# evpr_mainboard.net
KiCad netlist of a schematic drawn in EAGLE
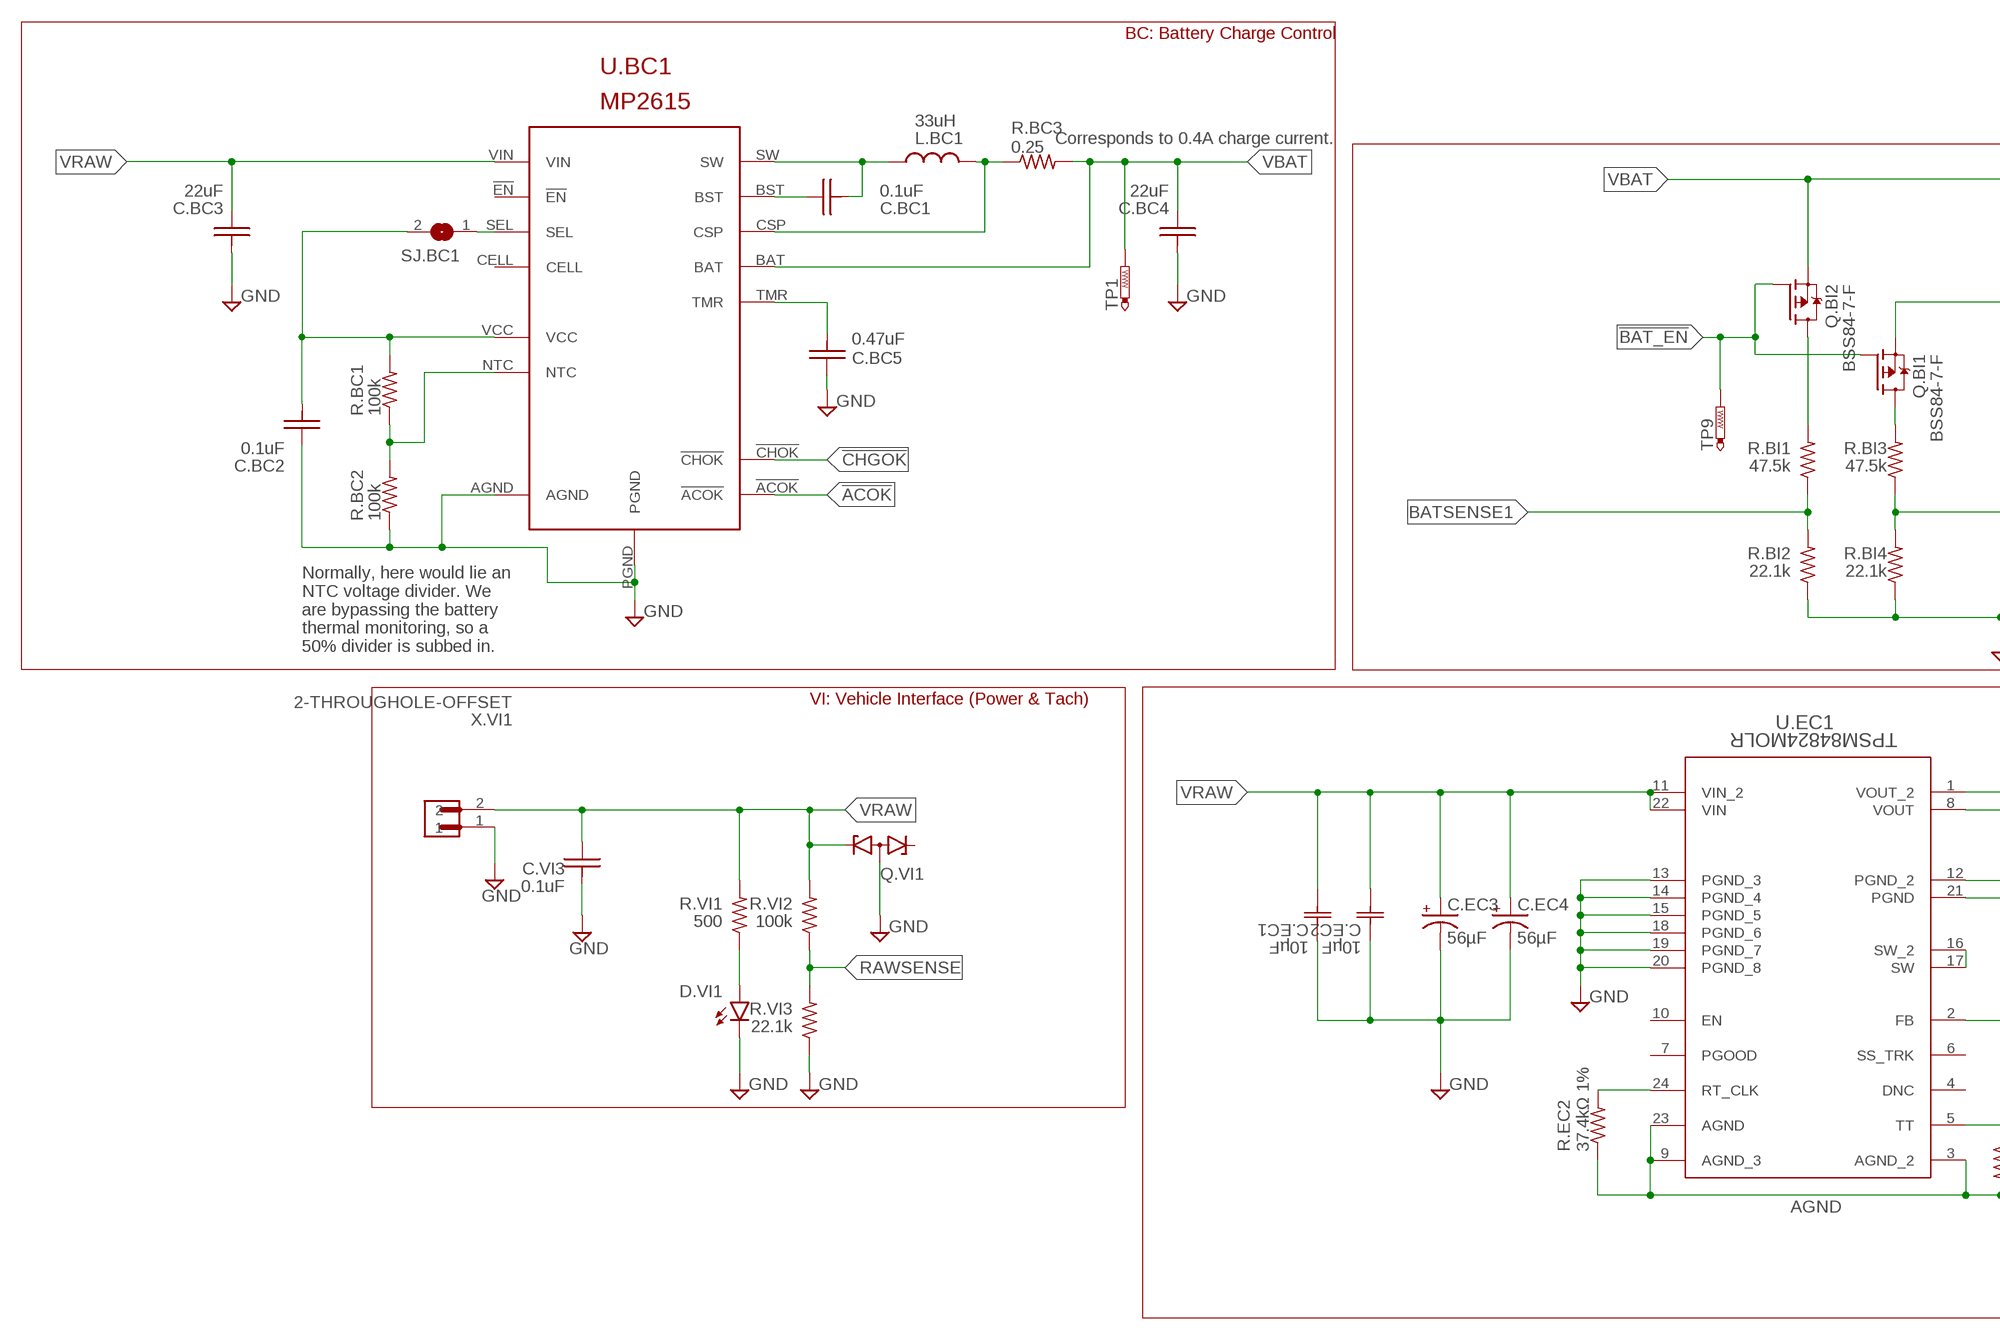
[diagram p0: schematic, sheet 1, part 1 of 2]
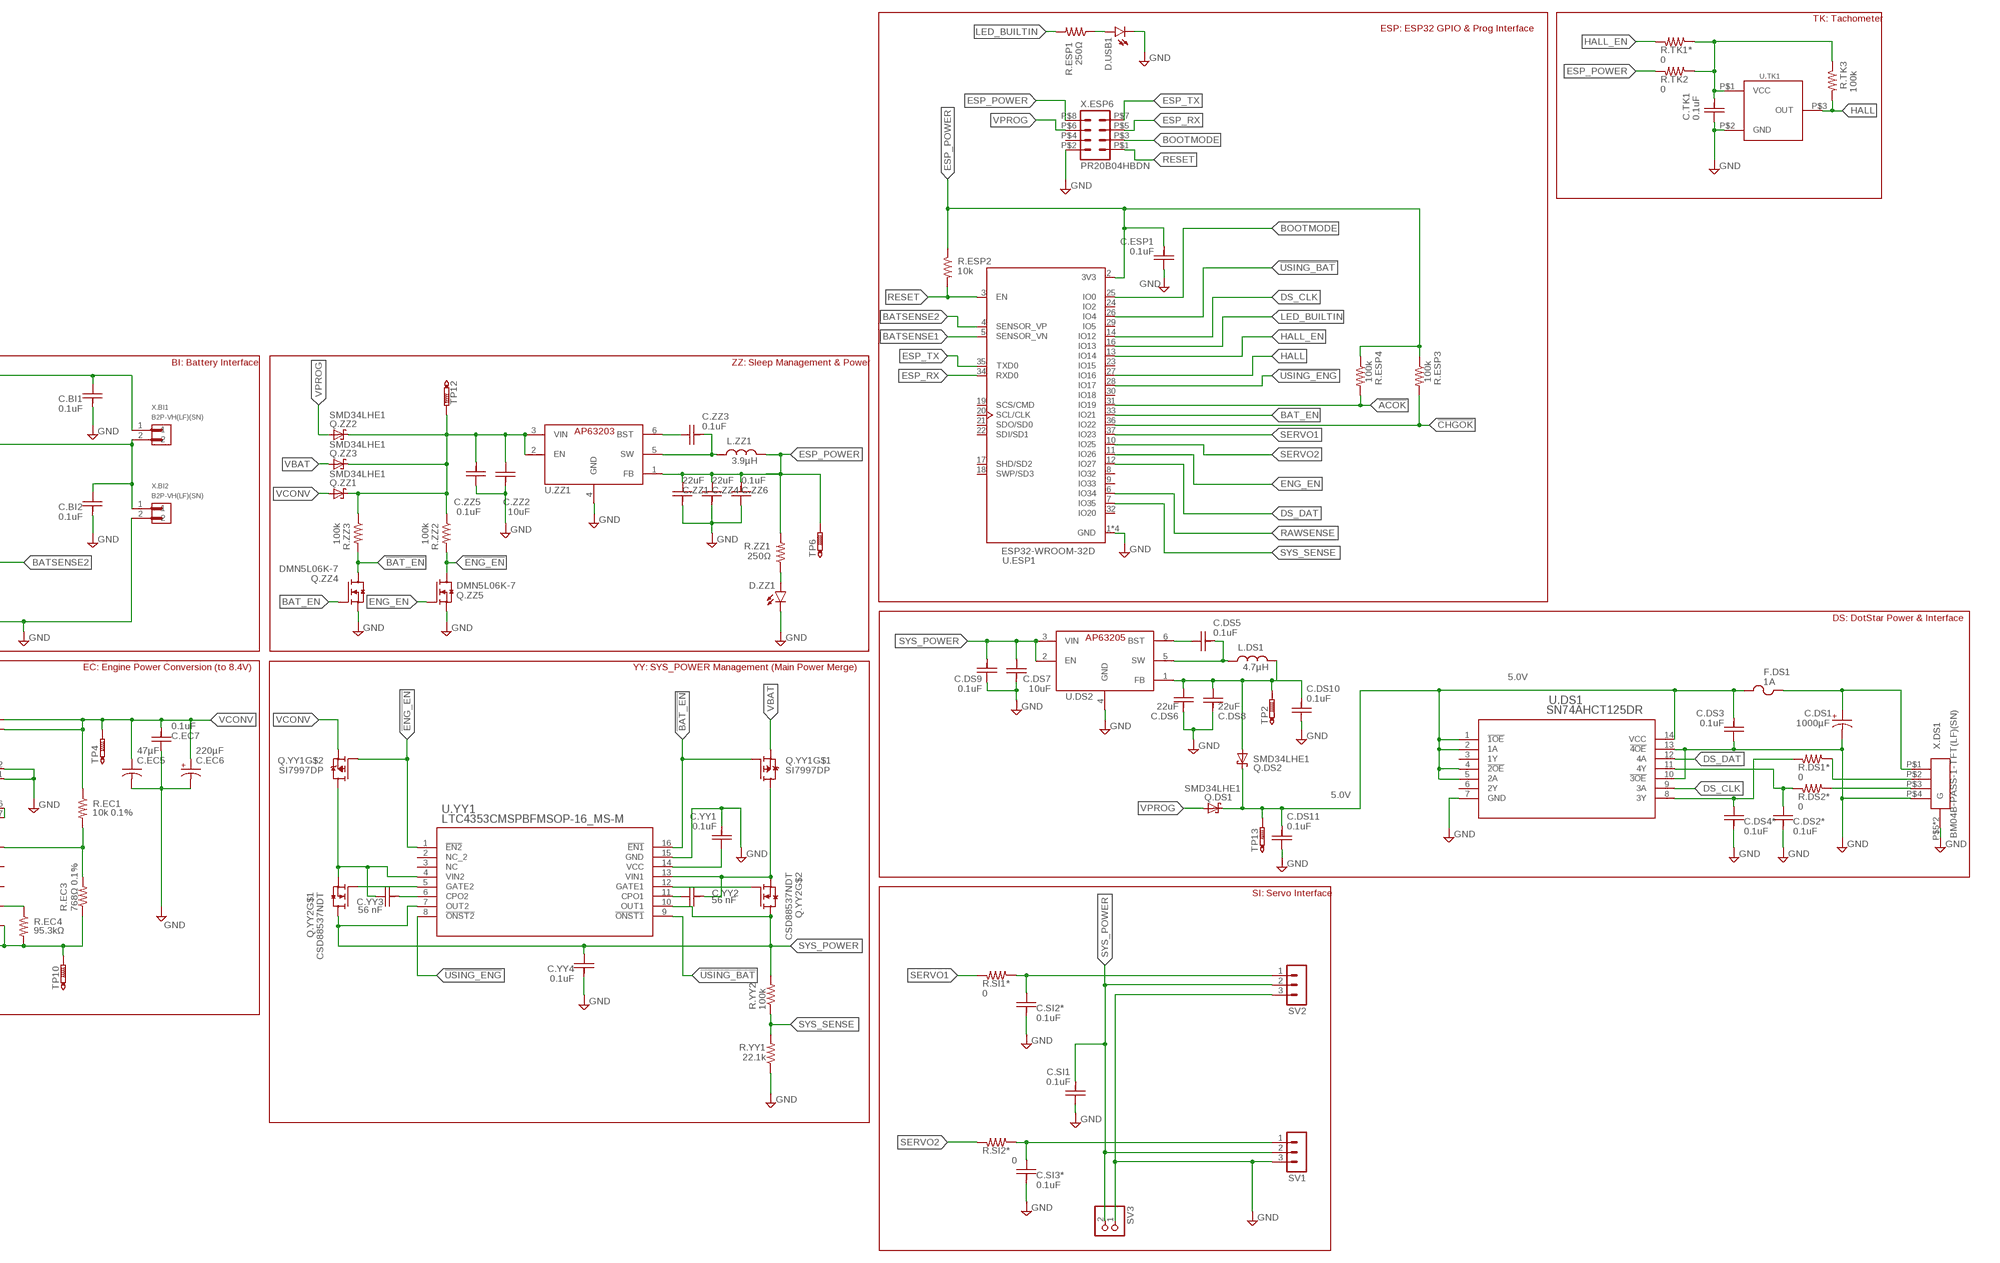
[diagram p1: schematic, sheet 1, part 2 of 2]

(export (version "E")
  (design (tool "Eeschema 10.0.6"))
  (components
    (comp (ref "C.BC1")
      (value "0.1uF")
      (footprint "eagle-import:C0603")
      (libsource (lib "eagle-import") (part "C0603"))
    )
    (comp (ref "C.BC2")
      (value "0.1uF")
      (footprint "eagle-import:C0603")
      (libsource (lib "eagle-import") (part "C0603"))
    )
    (comp (ref "C.BC3")
      (value "22uF")
      (footprint "eagle-import:C0603")
      (libsource (lib "eagle-import") (part "C0603"))
    )
    (comp (ref "C.BC4")
      (value "22uF")
      (footprint "eagle-import:C0603")
      (libsource (lib "eagle-import") (part "C0603"))
    )
    (comp (ref "C.BC5")
      (value "0.47uF")
      (footprint "eagle-import:C0603")
      (libsource (lib "eagle-import") (part "C0603"))
    )
    (comp (ref "C.BI1")
      (value "0.1uF")
      (footprint "eagle-import:C0603")
      (libsource (lib "eagle-import") (part "C0603"))
    )
    (comp (ref "C.BI2")
      (value "0.1uF")
      (footprint "eagle-import:C0603")
      (libsource (lib "eagle-import") (part "C0603"))
    )
    (comp (ref "C.DS1")
      (value "1000µF")
      (footprint "eagle-import:810RADCAN")
      (libsource (lib "eagle-import") (part "810RADCAP"))
    )
    (comp (ref "C.DS2*")
      (value "0.1uF")
      (footprint "eagle-import:C0603")
      (libsource (lib "eagle-import") (part "C0603"))
    )
    (comp (ref "C.DS3")
      (value "0.1uF")
      (footprint "eagle-import:C0603")
      (libsource (lib "eagle-import") (part "C0603"))
    )
    (comp (ref "C.DS4*")
      (value "0.1uF")
      (footprint "eagle-import:C0603")
      (libsource (lib "eagle-import") (part "C0603"))
    )
    (comp (ref "C.DS5")
      (value "0.1uF")
      (footprint "eagle-import:C0603")
      (libsource (lib "eagle-import") (part "C0603"))
    )
    (comp (ref "C.DS6")
      (value "22uF")
      (footprint "eagle-import:C0603")
      (libsource (lib "eagle-import") (part "C0603"))
    )
    (comp (ref "C.DS7")
      (value "10uF")
      (footprint "eagle-import:C0603")
      (libsource (lib "eagle-import") (part "C0603"))
    )
    (comp (ref "C.DS8")
      (value "22uF")
      (footprint "eagle-import:C0603")
      (libsource (lib "eagle-import") (part "C0603"))
    )
    (comp (ref "C.DS9")
      (value "0.1uF")
      (footprint "eagle-import:C0603")
      (libsource (lib "eagle-import") (part "C0603"))
    )
    (comp (ref "C.DS10")
      (value "0.1uF")
      (footprint "eagle-import:C0603")
      (libsource (lib "eagle-import") (part "C0603"))
    )
    (comp (ref "C.DS11")
      (value "0.1uF")
      (footprint "eagle-import:C0603")
      (libsource (lib "eagle-import") (part "C0603"))
    )
    (comp (ref "C.EC1")
      (value "10µF")
      (footprint "eagle-import:CAP_3225")
      (libsource (lib "eagle-import") (part "C3225X7R1E106K250AC"))
    )
    (comp (ref "C.EC2")
      (value "10µF")
      (footprint "eagle-import:CAP_3225")
      (libsource (lib "eagle-import") (part "C3225X7R1E106K250AC"))
    )
    (comp (ref "C.EC3")
      (value "56µF")
      (footprint "eagle-import:OSCON_SVPF_6.3MM")
      (libsource (lib "eagle-import") (part "6.3MMCAP"))
    )
    (comp (ref "C.EC4")
      (value "56µF")
      (footprint "eagle-import:OSCON_SVPF_6.3MM")
      (libsource (lib "eagle-import") (part "6.3MMCAP"))
    )
    (comp (ref "C.EC5")
      (value "47µF")
      (footprint "eagle-import:C1210")
      (libsource (lib "eagle-import") (part "C-USC1210"))
    )
    (comp (ref "C.EC6")
      (value "220µF")
      (footprint "eagle-import:C6CYLCAP")
      (libsource (lib "eagle-import") (part "WURTH875115352003"))
    )
    (comp (ref "C.EC7")
      (value "0.1uF")
      (footprint "eagle-import:C0603")
      (libsource (lib "eagle-import") (part "C0603"))
    )
    (comp (ref "C.ESP1")
      (value "0.1uF")
      (footprint "eagle-import:C0603")
      (libsource (lib "eagle-import") (part "C0603"))
    )
    (comp (ref "C.SI1")
      (value "0.1uF")
      (footprint "eagle-import:C0603")
      (libsource (lib "eagle-import") (part "C0603"))
    )
    (comp (ref "C.SI2*")
      (value "0.1uF")
      (footprint "eagle-import:C0603")
      (libsource (lib "eagle-import") (part "C0603"))
    )
    (comp (ref "C.SI3*")
      (value "0.1uF")
      (footprint "eagle-import:C0603")
      (libsource (lib "eagle-import") (part "C0603"))
    )
    (comp (ref "C.TK1")
      (value "0.1uF")
      (footprint "eagle-import:C0603")
      (libsource (lib "eagle-import") (part "C0603"))
    )
    (comp (ref "C.VI3")
      (value "0.1uF")
      (footprint "eagle-import:C0603")
      (libsource (lib "eagle-import") (part "C0603"))
    )
    (comp (ref "C.YY1")
      (value "0.1uF")
      (footprint "eagle-import:C0603")
      (libsource (lib "eagle-import") (part "C0603"))
    )
    (comp (ref "C.YY2")
      (value "56 nF")
      (footprint "eagle-import:C0603")
      (libsource (lib "eagle-import") (part "C0603"))
    )
    (comp (ref "C.YY3")
      (value "56 nF")
      (footprint "eagle-import:C0603")
      (libsource (lib "eagle-import") (part "C0603"))
    )
    (comp (ref "C.YY4")
      (value "0.1uF")
      (footprint "eagle-import:C0603")
      (libsource (lib "eagle-import") (part "C0603"))
    )
    (comp (ref "C.ZZ1")
      (value "22uF")
      (footprint "eagle-import:C0603")
      (libsource (lib "eagle-import") (part "C0603"))
    )
    (comp (ref "C.ZZ2")
      (value "10uF")
      (footprint "eagle-import:C0603")
      (libsource (lib "eagle-import") (part "C0603"))
    )
    (comp (ref "C.ZZ3")
      (value "0.1uF")
      (footprint "eagle-import:C0603")
      (libsource (lib "eagle-import") (part "C0603"))
    )
    (comp (ref "C.ZZ4")
      (value "22uF")
      (footprint "eagle-import:C0603")
      (libsource (lib "eagle-import") (part "C0603"))
    )
    (comp (ref "C.ZZ5")
      (value "0.1uF")
      (footprint "eagle-import:C0603")
      (libsource (lib "eagle-import") (part "C0603"))
    )
    (comp (ref "C.ZZ6")
      (value "0.1uF")
      (footprint "eagle-import:C0603")
      (libsource (lib "eagle-import") (part "C0603"))
    )
    (comp (ref "D.USB1")
      (value "LEDCHIP-LED0805")
      (footprint "eagle-import:CHIP-LED0805")
      (libsource (lib "eagle-import") (part "LEDCHIP-LED0805"))
    )
    (comp (ref "D.VI1")
      (value "LEDCHIP-LED0805")
      (footprint "eagle-import:CHIP-LED0805")
      (libsource (lib "eagle-import") (part "LEDCHIP-LED0805"))
    )
    (comp (ref "D.ZZ1")
      (value "LEDCHIP-LED0805")
      (footprint "eagle-import:CHIP-LED0805")
      (libsource (lib "eagle-import") (part "LEDCHIP-LED0805"))
    )
    (comp (ref "F.DS1")
      (value "1A")
      (footprint "eagle-import:C1-M")
      (fields (field (name "MANUFACTURER_PART_NUMBER") "C1Q 1"))
      (libsource (lib "eagle-import") (part "C1Q_1C1-M"))
    )
    (comp (ref "L.BC1")
      (value "33uH")
      (footprint "eagle-import:SRN5040TA")
      (libsource (lib "eagle-import") (part "SRN5040TA-330M"))
    )
    (comp (ref "L.DS1")
      (value "4.7µH")
      (footprint "eagle-import:SRR4818A-XXXX")
      (libsource (lib "eagle-import") (part "SRR4818A-XXXX"))
    )
    (comp (ref "L.ZZ1")
      (value "3.9µH")
      (footprint "eagle-import:SRR4818A-XXXX")
      (libsource (lib "eagle-import") (part "SRR4818A-XXXX"))
    )
    (comp (ref "Q.BI1")
      (value "BSS84-7-F")
      (footprint "eagle-import:SOT23")
      (libsource (lib "eagle-import") (part "BSS84-7-F"))
    )
    (comp (ref "Q.BI2")
      (value "BSS84-7-F")
      (footprint "eagle-import:SOT23")
      (libsource (lib "eagle-import") (part "BSS84-7-F"))
    )
    (comp (ref "Q.DS1")
      (value "SMD34LHE1")
      (footprint "eagle-import:SOD-123HE1")
      (libsource (lib "eagle-import") (part "SMD34LHE1"))
    )
    (comp (ref "Q.DS2")
      (value "SMD34LHE1")
      (footprint "eagle-import:SOD-123HE1")
      (libsource (lib "eagle-import") (part "SMD34LHE1"))
    )
    (comp (ref "Q.VI1")
      (value "VESD16A2-03G-G3-08")
      (footprint "eagle-import:SOT23")
      (libsource (lib "eagle-import") (part "VESD16A2-03G-G3-08"))
    )
    (comp (ref "Q.YY1")
      (value "SI7997DP")
      (footprint "eagle-import:POWERPAK_SO8DUAL")
      (libsource (lib "eagle-import") (part "SI7997DP"))
    )
    (comp (ref "Q.YY2")
      (value "CSD88537NDT")
      (footprint "eagle-import:SOIC8")
      (fields (field (name "COMPONENT") "CSD88537NDT"))
      (libsource (lib "eagle-import") (part "CSD88537NDT"))
    )
    (comp (ref "Q.ZZ1")
      (value "SMD34LHE1")
      (footprint "eagle-import:SOD-123HE1")
      (libsource (lib "eagle-import") (part "SMD34LHE1"))
    )
    (comp (ref "Q.ZZ2")
      (value "SMD34LHE1")
      (footprint "eagle-import:SOD-123HE1")
      (libsource (lib "eagle-import") (part "SMD34LHE1"))
    )
    (comp (ref "Q.ZZ3")
      (value "SMD34LHE1")
      (footprint "eagle-import:SOD-123HE1")
      (libsource (lib "eagle-import") (part "SMD34LHE1"))
    )
    (comp (ref "Q.ZZ4")
      (value "DMN5L06K-7")
      (footprint "eagle-import:SOT23")
      (libsource (lib "eagle-import") (part "DMN5L06K-7"))
    )
    (comp (ref "Q.ZZ5")
      (value "DMN5L06K-7")
      (footprint "eagle-import:SOT23")
      (libsource (lib "eagle-import") (part "DMN5L06K-7"))
    )
    (comp (ref "R.BC1")
      (value "100k")
      (footprint "eagle-import:R0603")
      (libsource (lib "eagle-import") (part "R0603"))
    )
    (comp (ref "R.BC2")
      (value "100k")
      (footprint "eagle-import:R0603")
      (libsource (lib "eagle-import") (part "R0603"))
    )
    (comp (ref "R.BC3")
      (value "0.25")
      (footprint "eagle-import:R0603")
      (libsource (lib "eagle-import") (part "R0603"))
    )
    (comp (ref "R.BI1")
      (value "47.5k")
      (footprint "eagle-import:R0603")
      (libsource (lib "eagle-import") (part "R0603"))
    )
    (comp (ref "R.BI2")
      (value "22.1k")
      (footprint "eagle-import:R0603")
      (libsource (lib "eagle-import") (part "R0603"))
    )
    (comp (ref "R.BI3")
      (value "47.5k")
      (footprint "eagle-import:R0603")
      (libsource (lib "eagle-import") (part "R0603"))
    )
    (comp (ref "R.BI4")
      (value "22.1k")
      (footprint "eagle-import:R0603")
      (libsource (lib "eagle-import") (part "R0603"))
    )
    (comp (ref "R.DS1*")
      (value "0")
      (footprint "eagle-import:R0603")
      (libsource (lib "eagle-import") (part "R0603"))
    )
    (comp (ref "R.DS2*")
      (value "0")
      (footprint "eagle-import:R0603")
      (libsource (lib "eagle-import") (part "R0603"))
    )
    (comp (ref "R.EC1")
      (value "10k 0.1%")
      (footprint "eagle-import:R0603")
      (libsource (lib "eagle-import") (part "R0603"))
    )
    (comp (ref "R.EC2")
      (value "37.4kΩ 1%")
      (footprint "eagle-import:R0603")
      (libsource (lib "eagle-import") (part "R0603"))
    )
    (comp (ref "R.EC3")
      (value "768Ω 0.1%")
      (footprint "eagle-import:R0603")
      (libsource (lib "eagle-import") (part "R0603"))
    )
    (comp (ref "R.EC4")
      (value "95.3kΩ")
      (footprint "eagle-import:R0603")
      (libsource (lib "eagle-import") (part "R0603"))
    )
    (comp (ref "R.ESP1")
      (value "250Ω")
      (footprint "eagle-import:R0603")
      (libsource (lib "eagle-import") (part "R0603"))
    )
    (comp (ref "R.ESP2")
      (value "10k")
      (footprint "eagle-import:R0603")
      (libsource (lib "eagle-import") (part "R0603"))
    )
    (comp (ref "R.ESP3")
      (value "100k")
      (footprint "eagle-import:R0603")
      (libsource (lib "eagle-import") (part "R0603"))
    )
    (comp (ref "R.ESP4")
      (value "100k")
      (footprint "eagle-import:R0603")
      (libsource (lib "eagle-import") (part "R0603"))
    )
    (comp (ref "R.SI1*")
      (value "0")
      (footprint "eagle-import:R0603")
      (libsource (lib "eagle-import") (part "R0603"))
    )
    (comp (ref "R.SI2*")
      (value "0")
      (footprint "eagle-import:R0603")
      (libsource (lib "eagle-import") (part "R0603"))
    )
    (comp (ref "R.TK1*")
      (value "0")
      (footprint "eagle-import:R0603")
      (libsource (lib "eagle-import") (part "R0603"))
    )
    (comp (ref "R.TK2")
      (value "0")
      (footprint "eagle-import:R0603")
      (libsource (lib "eagle-import") (part "R0603"))
    )
    (comp (ref "R.TK3")
      (value "100k")
      (footprint "eagle-import:R0603")
      (libsource (lib "eagle-import") (part "R0603"))
    )
    (comp (ref "R.VI1")
      (value "500")
      (footprint "eagle-import:R0603")
      (libsource (lib "eagle-import") (part "R0603"))
    )
    (comp (ref "R.VI2")
      (value "100k")
      (footprint "eagle-import:R0603")
      (libsource (lib "eagle-import") (part "R0603"))
    )
    (comp (ref "R.VI3")
      (value "22.1k")
      (footprint "eagle-import:R0603")
      (libsource (lib "eagle-import") (part "R0603"))
    )
    (comp (ref "R.YY1")
      (value "22.1k")
      (footprint "eagle-import:R0603")
      (libsource (lib "eagle-import") (part "R0603"))
    )
    (comp (ref "R.YY2")
      (value "100k")
      (footprint "eagle-import:R0603")
      (libsource (lib "eagle-import") (part "R0603"))
    )
    (comp (ref "R.ZZ1")
      (value "250Ω")
      (footprint "eagle-import:R0603")
      (libsource (lib "eagle-import") (part "R0603"))
    )
    (comp (ref "R.ZZ2")
      (value "100k")
      (footprint "eagle-import:R0603")
      (libsource (lib "eagle-import") (part "R0603"))
    )
    (comp (ref "R.ZZ3")
      (value "100k")
      (footprint "eagle-import:R0603")
      (libsource (lib "eagle-import") (part "R0603"))
    )
    (comp (ref "SJ.BC1")
      (value "SJ")
      (footprint "eagle-import:SJ")
      (libsource (lib "eagle-import") (part "SJ"))
    )
    (comp (ref "SV1")
      (value "MA03-1")
      (footprint "eagle-import:MA03-1")
      (libsource (lib "eagle-import") (part "MA03-1"))
    )
    (comp (ref "SV2")
      (value "MA03-1")
      (footprint "eagle-import:MA03-1")
      (libsource (lib "eagle-import") (part "MA03-1"))
    )
    (comp (ref "SV3")
      (value "PINHD-1X2")
      (footprint "eagle-import:1X02")
      (libsource (lib "eagle-import") (part "PINHD-1X2"))
    )
    (comp (ref "TP1")
      (value "PTR1TP10R")
      (footprint "eagle-import:TP10R")
      (libsource (lib "eagle-import") (part "PTR1TP10R"))
    )
    (comp (ref "TP2")
      (value "PTR1TP10R")
      (footprint "eagle-import:TP10R")
      (libsource (lib "eagle-import") (part "PTR1TP10R"))
    )
    (comp (ref "TP4")
      (value "PTR1TP10R")
      (footprint "eagle-import:TP10R")
      (libsource (lib "eagle-import") (part "PTR1TP10R"))
    )
    (comp (ref "TP6")
      (value "PTR1TP10R")
      (footprint "eagle-import:TP10R")
      (libsource (lib "eagle-import") (part "PTR1TP10R"))
    )
    (comp (ref "TP9")
      (value "PTR1TP10R")
      (footprint "eagle-import:TP10R")
      (libsource (lib "eagle-import") (part "PTR1TP10R"))
    )
    (comp (ref "TP10")
      (value "PTR1TP10R")
      (footprint "eagle-import:TP10R")
      (libsource (lib "eagle-import") (part "PTR1TP10R"))
    )
    (comp (ref "TP12")
      (value "PTR1TP10R")
      (footprint "eagle-import:TP10R")
      (libsource (lib "eagle-import") (part "PTR1TP10R"))
    )
    (comp (ref "TP13")
      (value "PTR1TP10R")
      (footprint "eagle-import:TP10R")
      (libsource (lib "eagle-import") (part "PTR1TP10R"))
    )
    (comp (ref "U.BC1")
      (value "MP2615")
      (footprint "eagle-import:QFN16")
      (libsource (lib "eagle-import") (part "MP2615"))
    )
    (comp (ref "U.DS1")
      (value "SN74AHCT125DR")
      (footprint "eagle-import:D14")
      (libsource (lib "eagle-import") (part "SN74AHCT125DR"))
    )
    (comp (ref "U.DS2")
      (value "AP63205")
      (footprint "eagle-import:TSOT23-6")
      (libsource (lib "eagle-import") (part "AP63205"))
    )
    (comp (ref "U.EC1")
      (value "TPSM84824MOLR")
      (footprint "eagle-import:MOL0024A")
      (libsource (lib "eagle-import") (part "TPSM84824MOLR"))
    )
    (comp (ref "U.ESP1")
      (value "ESP32-WROOM-32D")
      (footprint "eagle-import:MODULE_ESP32-WROOM-32D")
      (fields (field (name "MF") "Espressif Systems"))
      (libsource (lib "eagle-import") (part "ESP32-WROOM-32D"))
    )
    (comp (ref "U.TK1")
      (value "HALLEFFECT")
      (footprint "eagle-import:1.27MMHALLEFECT")
      (libsource (lib "eagle-import") (part "HALLEFFECT"))
    )
    (comp (ref "U.YY1")
      (value "LTC4353CMSPBFMSOP-16_MS-M")
      (footprint "eagle-import:MSOP-16_MS-M")
      (fields (field (name "MANUFACTURER_PART_NUMBER") "LTC4353CMS#PBF"))
      (libsource (lib "eagle-import") (part "LTC4353CMSPBFMSOP-16_MS-M"))
    )
    (comp (ref "U.ZZ1")
      (value "AP63203")
      (footprint "eagle-import:TSOT23-6")
      (libsource (lib "eagle-import") (part "AP63203"))
    )
    (comp (ref "X.BI1")
      (value "B2P-VH(LF)(SN)")
      (footprint "eagle-import:B2P-VH(LF)(SN)")
      (fields (field (name "MF") "JST Sales") (field (name "MP") "B2P-VH_LF__SN_"))
      (libsource (lib "eagle-import") (part "B2P-VH(LF)(SN)"))
    )
    (comp (ref "X.BI2")
      (value "B2P-VH(LF)(SN)")
      (footprint "eagle-import:B2P-VH(LF)(SN)")
      (fields (field (name "MF") "JST Sales") (field (name "MP") "B2P-VH_LF__SN_"))
      (libsource (lib "eagle-import") (part "B2P-VH(LF)(SN)"))
    )
    (comp (ref "X.DS1")
      (value "BM04B-PASS-1-TFT(LF)(SN)")
      (footprint "eagle-import:BM04B-PASS-1-TFT(LF)(SN)")
      (libsource (lib "eagle-import") (part "BM04B-PASS-1-TFT(LF)(SN)"))
    )
    (comp (ref "X.ESP6")
      (value "PR20B04HBDN")
      (footprint "eagle-import:PR20B04HBDN")
      (libsource (lib "eagle-import") (part "PR20B04HBDN"))
    )
    (comp (ref "X.VI1")
      (value "2-THROUGHOLE-OFFSET")
      (footprint "eagle-import:2-THROUGH-HOLE-LARGE-OFFSET")
      (libsource (lib "eagle-import") (part "2-THROUGHOLE-OFFSET"))
    )
  )
  (nets
    (net (code "1") (name "/5.0V") (class "Default")
      (node (ref "C.DS11") (pin "2") (pinfunction "2_2") (pintype "passive"))
      (node (ref "C.DS3") (pin "2") (pinfunction "2_2") (pintype "passive"))
      (node (ref "F.DS1") (pin "1") (pinfunction "1_1") (pintype "passive"))
      (node (ref "Q.DS1") (pin "C") (pinfunction "C_C") (pintype "passive"))
      (node (ref "Q.DS2") (pin "C") (pinfunction "C_C") (pintype "passive"))
      (node (ref "TP13") (pin "TP") (pinfunction "TP_TP") (pintype "input"))
      (node (ref "U.DS1") (pin "1") (pinfunction "~{1OE}_1") (pintype "input"))
      (node (ref "U.DS1") (pin "14") (pinfunction "VCC_14") (pintype "power_in"))
      (node (ref "U.DS1") (pin "2") (pinfunction "1A_2") (pintype "input"))
      (node (ref "U.DS1") (pin "4") (pinfunction "~{2OE}_4") (pintype "input"))
      (node (ref "U.DS1") (pin "5") (pinfunction "2A_5") (pintype "input"))
    )
    (net (code "2") (name "/AGND") (class "Default")
      (node (ref "R.EC2") (pin "1") (pinfunction "1_1") (pintype "passive"))
      (node (ref "R.EC3") (pin "1") (pinfunction "1_1") (pintype "passive"))
      (node (ref "R.EC4") (pin "2") (pinfunction "2_2") (pintype "passive"))
      (node (ref "TP10") (pin "TP") (pinfunction "TP_TP") (pintype "input"))
      (node (ref "U.EC1") (pin "23") (pinfunction "AGND_23") (pintype "power_in"))
      (node (ref "U.EC1") (pin "3") (pinfunction "AGND_2_3") (pintype "power_in"))
      (node (ref "U.EC1") (pin "9") (pinfunction "AGND_3_9") (pintype "power_in"))
    )
    (net (code "3") (name "/~{ACOK}") (class "Default")
      (node (ref "R.ESP4") (pin "2") (pinfunction "2_2") (pintype "passive"))
      (node (ref "U.BC1") (pin "!ACOK") (pinfunction "~{ACOK}_!ACOK") (pintype "bidirectional"))
      (node (ref "U.ESP1") (pin "31") (pinfunction "IO19_31") (pintype "bidirectional"))
    )
    (net (code "4") (name "/~{BAT_EN}") (class "Default")
      (node (ref "Q.BI1") (pin "1") (pinfunction "G_1") (pintype "passive"))
      (node (ref "Q.BI2") (pin "1") (pinfunction "G_1") (pintype "passive"))
      (node (ref "Q.YY1") (pin "P$2") (pinfunction "G_P$2") (pintype "passive"))
      (node (ref "Q.ZZ4") (pin "3") (pinfunction "D_3") (pintype "passive"))
      (node (ref "R.ZZ3") (pin "2") (pinfunction "2_2") (pintype "passive"))
      (node (ref "TP9") (pin "TP") (pinfunction "TP_TP") (pintype "input"))
      (node (ref "U.YY1") (pin "16") (pinfunction "~{EN1}_16") (pintype "input"))
    )
    (net (code "5") (name "/~{CHGOK}") (class "Default")
      (node (ref "R.ESP3") (pin "2") (pinfunction "2_2") (pintype "passive"))
      (node (ref "U.BC1") (pin "!CHOK") (pinfunction "~{CHOK}_!CHOK") (pintype "bidirectional"))
      (node (ref "U.ESP1") (pin "36") (pinfunction "IO22_36") (pintype "bidirectional"))
    )
    (net (code "6") (name "/~{ENG_EN}") (class "Default")
      (node (ref "Q.YY1") (pin "P$4") (pinfunction "G_P$4") (pintype "passive"))
      (node (ref "Q.ZZ5") (pin "3") (pinfunction "D_3") (pintype "passive"))
      (node (ref "R.ZZ2") (pin "2") (pinfunction "2_2") (pintype "passive"))
      (node (ref "U.YY1") (pin "1") (pinfunction "~{EN2}_1") (pintype "input"))
    )
    (net (code "7") (name "/~{USING_BAT}") (class "Default")
      (node (ref "U.ESP1") (pin "26") (pinfunction "IO4_26") (pintype "bidirectional"))
      (node (ref "U.YY1") (pin "9") (pinfunction "~{ONST1}_9") (pintype "output"))
    )
    (net (code "8") (name "/~{USING_ENG}") (class "Default")
      (node (ref "U.ESP1") (pin "28") (pinfunction "IO17_28") (pintype "bidirectional"))
      (node (ref "U.YY1") (pin "8") (pinfunction "~{ONST2}_8") (pintype "output"))
    )
    (net (code "9") (name "BATSENSE1") (class "Default")
      (node (ref "R.BI1") (pin "1") (pinfunction "1_1") (pintype "passive"))
      (node (ref "R.BI2") (pin "2") (pinfunction "2_2") (pintype "passive"))
      (node (ref "U.ESP1") (pin "5") (pinfunction "SENSOR_VN_5") (pintype "input"))
    )
    (net (code "10") (name "BATSENSE2") (class "Default")
      (node (ref "R.BI3") (pin "1") (pinfunction "1_1") (pintype "passive"))
      (node (ref "R.BI4") (pin "2") (pinfunction "2_2") (pintype "passive"))
      (node (ref "U.ESP1") (pin "4") (pinfunction "SENSOR_VP_4") (pintype "input"))
    )
    (net (code "11") (name "BAT_EN") (class "Default")
      (node (ref "Q.ZZ4") (pin "1") (pinfunction "G_1") (pintype "passive"))
      (node (ref "U.ESP1") (pin "33") (pinfunction "IO21_33") (pintype "bidirectional"))
    )
    (net (code "12") (name "BOOTMODE") (class "Default")
      (node (ref "U.ESP1") (pin "25") (pinfunction "IO0_25") (pintype "bidirectional"))
      (node (ref "X.ESP6") (pin "P$3") (pinfunction "3_P$3") (pintype "passive"))
    )
    (net (code "13") (name "DS_CLK") (class "Default")
      (node (ref "U.DS1") (pin "9") (pinfunction "3A_9") (pintype "input"))
      (node (ref "U.ESP1") (pin "14") (pinfunction "IO12_14") (pintype "bidirectional"))
    )
    (net (code "14") (name "DS_DAT") (class "Default")
      (node (ref "U.DS1") (pin "12") (pinfunction "4A_12") (pintype "input"))
      (node (ref "U.ESP1") (pin "12") (pinfunction "IO27_12") (pintype "bidirectional"))
    )
    (net (code "15") (name "ENG_EN") (class "Default")
      (node (ref "Q.ZZ5") (pin "1") (pinfunction "G_1") (pintype "passive"))
      (node (ref "U.ESP1") (pin "11") (pinfunction "IO26_11") (pintype "bidirectional"))
    )
    (net (code "16") (name "ESP_POWER") (class "Default")
      (node (ref "C.ESP1") (pin "2") (pinfunction "2_2") (pintype "passive"))
      (node (ref "C.ZZ1") (pin "1") (pinfunction "1_1") (pintype "passive"))
      (node (ref "C.ZZ4") (pin "1") (pinfunction "1_1") (pintype "passive"))
      (node (ref "C.ZZ6") (pin "2") (pinfunction "2_2") (pintype "passive"))
      (node (ref "L.ZZ1") (pin "P$2") (pinfunction "2_P$2") (pintype "passive"))
      (node (ref "R.ESP2") (pin "1") (pinfunction "1_1") (pintype "passive"))
      (node (ref "R.ESP3") (pin "1") (pinfunction "1_1") (pintype "passive"))
      (node (ref "R.ESP4") (pin "1") (pinfunction "1_1") (pintype "passive"))
      (node (ref "R.TK2") (pin "2") (pinfunction "2_2") (pintype "passive"))
      (node (ref "R.ZZ1") (pin "2") (pinfunction "2_2") (pintype "passive"))
      (node (ref "TP6") (pin "TP") (pinfunction "TP_TP") (pintype "input"))
      (node (ref "U.ESP1") (pin "2") (pinfunction "3V3_2") (pintype "power_in"))
      (node (ref "U.ZZ1") (pin "1") (pinfunction "FB_1") (pintype "bidirectional"))
      (node (ref "X.ESP6") (pin "P$8") (pinfunction "8_P$8") (pintype "passive"))
    )
    (net (code "17") (name "ESP_RX") (class "Default")
      (node (ref "U.ESP1") (pin "34") (pinfunction "RXD0_34") (pintype "bidirectional"))
      (node (ref "X.ESP6") (pin "P$5") (pinfunction "5_P$5") (pintype "passive"))
    )
    (net (code "18") (name "ESP_TX") (class "Default")
      (node (ref "U.ESP1") (pin "35") (pinfunction "TXD0_35") (pintype "bidirectional"))
      (node (ref "X.ESP6") (pin "P$7") (pinfunction "7_P$7") (pintype "passive"))
    )
    (net (code "19") (name "GND") (class "Default")
      (node (ref "C.BC2") (pin "1") (pinfunction "1_1") (pintype "passive"))
      (node (ref "C.BC3") (pin "2") (pinfunction "2_2") (pintype "passive"))
      (node (ref "C.BC4") (pin "2") (pinfunction "2_2") (pintype "passive"))
      (node (ref "C.BC5") (pin "1") (pinfunction "1_1") (pintype "passive"))
      (node (ref "C.BI1") (pin "2") (pinfunction "2_2") (pintype "passive"))
      (node (ref "C.BI2") (pin "2") (pinfunction "2_2") (pintype "passive"))
      (node (ref "C.DS1") (pin "C$2") (pinfunction "-_C$2") (pintype "passive"))
      (node (ref "C.DS10") (pin "1") (pinfunction "1_1") (pintype "passive"))
      (node (ref "C.DS11") (pin "1") (pinfunction "1_1") (pintype "passive"))
      (node (ref "C.DS2*") (pin "2") (pinfunction "2_2") (pintype "passive"))
      (node (ref "C.DS3") (pin "1") (pinfunction "1_1") (pintype "passive"))
      (node (ref "C.DS4*") (pin "2") (pinfunction "2_2") (pintype "passive"))
      (node (ref "C.DS6") (pin "2") (pinfunction "2_2") (pintype "passive"))
      (node (ref "C.DS7") (pin "2") (pinfunction "2_2") (pintype "passive"))
      (node (ref "C.DS8") (pin "2") (pinfunction "2_2") (pintype "passive"))
      (node (ref "C.DS9") (pin "1") (pinfunction "1_1") (pintype "passive"))
      (node (ref "C.EC1") (pin "1") (pinfunction "1_1") (pintype "passive"))
      (node (ref "C.EC2") (pin "1") (pinfunction "1_1") (pintype "passive"))
      (node (ref "C.EC3") (pin "-") (pinfunction "-_-") (pintype "passive"))
      (node (ref "C.EC4") (pin "-") (pinfunction "-_-") (pintype "passive"))
      (node (ref "C.EC5") (pin "2") (pinfunction "2_2") (pintype "passive"))
      (node (ref "C.EC6") (pin "P$1") (pinfunction "-_P$1") (pintype "passive"))
      (node (ref "C.EC7") (pin "1") (pinfunction "1_1") (pintype "passive"))
      (node (ref "C.ESP1") (pin "1") (pinfunction "1_1") (pintype "passive"))
      (node (ref "C.SI1") (pin "1") (pinfunction "1_1") (pintype "passive"))
      (node (ref "C.SI2*") (pin "2") (pinfunction "2_2") (pintype "passive"))
      (node (ref "C.SI3*") (pin "2") (pinfunction "2_2") (pintype "passive"))
      (node (ref "C.TK1") (pin "1") (pinfunction "1_1") (pintype "passive"))
      (node (ref "C.VI3") (pin "2") (pinfunction "2_2") (pintype "passive"))
      (node (ref "C.YY1") (pin "2") (pinfunction "2_2") (pintype "passive"))
      (node (ref "C.YY4") (pin "2") (pinfunction "2_2") (pintype "passive"))
      (node (ref "C.ZZ1") (pin "2") (pinfunction "2_2") (pintype "passive"))
      (node (ref "C.ZZ2") (pin "2") (pinfunction "2_2") (pintype "passive"))
      (node (ref "C.ZZ4") (pin "2") (pinfunction "2_2") (pintype "passive"))
      (node (ref "C.ZZ5") (pin "1") (pinfunction "1_1") (pintype "passive"))
      (node (ref "C.ZZ6") (pin "1") (pinfunction "1_1") (pintype "passive"))
      (node (ref "D.USB1") (pin "C") (pinfunction "C_C") (pintype "passive"))
      (node (ref "D.VI1") (pin "C") (pinfunction "C_C") (pintype "passive"))
      (node (ref "D.ZZ1") (pin "C") (pinfunction "C_C") (pintype "passive"))
      (node (ref "Q.VI1") (pin "3") (pinfunction "AA_3") (pintype "passive"))
      (node (ref "Q.ZZ4") (pin "2") (pinfunction "S_2") (pintype "passive"))
      (node (ref "Q.ZZ5") (pin "2") (pinfunction "S_2") (pintype "passive"))
      (node (ref "R.BC2") (pin "1") (pinfunction "1_1") (pintype "passive"))
      (node (ref "R.BI2") (pin "1") (pinfunction "1_1") (pintype "passive"))
      (node (ref "R.BI4") (pin "1") (pinfunction "1_1") (pintype "passive"))
      (node (ref "R.VI3") (pin "1") (pinfunction "1_1") (pintype "passive"))
      (node (ref "R.YY1") (pin "1") (pinfunction "1_1") (pintype "passive"))
      (node (ref "SV1") (pin "3") (pinfunction "3_3") (pintype "passive"))
      (node (ref "SV2") (pin "3") (pinfunction "3_3") (pintype "passive"))
      (node (ref "SV3") (pin "1") (pinfunction "1_1") (pintype "passive"))
      (node (ref "U.BC1") (pin "AGND") (pinfunction "AGND_AGND") (pintype "bidirectional"))
      (node (ref "U.BC1") (pin "PGND") (pinfunction "PGND_PGND") (pintype "bidirectional"))
      (node (ref "U.DS1") (pin "10") (pinfunction "~{3OE}_10") (pintype "input"))
      (node (ref "U.DS1") (pin "13") (pinfunction "~{4OE}_13") (pintype "input"))
      (node (ref "U.DS1") (pin "7") (pinfunction "GND_7") (pintype "power_in"))
      (node (ref "U.DS2") (pin "4") (pinfunction "GND_4") (pintype "bidirectional"))
      (node (ref "U.EC1") (pin "12") (pinfunction "PGND_2_12") (pintype "power_in"))
      (node (ref "U.EC1") (pin "13") (pinfunction "PGND_3_13") (pintype "power_in"))
      (node (ref "U.EC1") (pin "14") (pinfunction "PGND_4_14") (pintype "power_in"))
      (node (ref "U.EC1") (pin "15") (pinfunction "PGND_5_15") (pintype "power_in"))
      (node (ref "U.EC1") (pin "18") (pinfunction "PGND_6_18") (pintype "power_in"))
      (node (ref "U.EC1") (pin "19") (pinfunction "PGND_7_19") (pintype "power_in"))
      (node (ref "U.EC1") (pin "20") (pinfunction "PGND_8_20") (pintype "power_in"))
      (node (ref "U.EC1") (pin "21") (pinfunction "PGND_21") (pintype "power_in"))
      (node (ref "U.ESP1") (pin "1") (pinfunction "GND_1") (pintype "power_in"))
      (node (ref "U.ESP1") (pin "15") (pinfunction "GND_15") (pintype "power_in"))
      (node (ref "U.ESP1") (pin "38") (pinfunction "GND_38") (pintype "power_in"))
      (node (ref "U.ESP1") (pin "39") (pinfunction "GND_39") (pintype "power_in"))
      (node (ref "U.TK1") (pin "P$2") (pinfunction "GND_P$2") (pintype "bidirectional"))
      (node (ref "U.YY1") (pin "15") (pinfunction "GND_15") (pintype "power_in"))
      (node (ref "U.ZZ1") (pin "4") (pinfunction "GND_4") (pintype "bidirectional"))
      (node (ref "X.BI2") (pin "2") (pinfunction "2_2") (pintype "passive"))
      (node (ref "X.DS1") (pin "P$4") (pinfunction "4_P$4") (pintype "passive"))
      (node (ref "X.DS1") (pin "P$5") (pinfunction "G_P$5") (pintype "passive"))
      (node (ref "X.DS1") (pin "P$6") (pinfunction "G_P$6") (pintype "passive"))
      (node (ref "X.ESP6") (pin "P$2") (pinfunction "2_P$2") (pintype "passive"))
      (node (ref "X.VI1") (pin "1") (pinfunction "1_1") (pintype "passive"))
    )
    (net (code "20") (name "HALL") (class "Default")
      (node (ref "R.TK3") (pin "2") (pinfunction "2_2") (pintype "passive"))
      (node (ref "U.ESP1") (pin "27") (pinfunction "IO16_27") (pintype "bidirectional"))
      (node (ref "U.TK1") (pin "P$3") (pinfunction "OUT_P$3") (pintype "bidirectional"))
    )
    (net (code "21") (name "HALL_EN") (class "Default")
      (node (ref "R.TK1*") (pin "2") (pinfunction "2_2") (pintype "passive"))
      (node (ref "U.ESP1") (pin "13") (pinfunction "IO14_13") (pintype "bidirectional"))
    )
    (net (code "22") (name "LED_BUILTIN") (class "Default")
      (node (ref "R.ESP1") (pin "2") (pinfunction "2_2") (pintype "passive"))
      (node (ref "U.ESP1") (pin "16") (pinfunction "IO13_16") (pintype "bidirectional"))
    )
    (net (code "23") (name "Net-(C.BC1-Pad1)") (class "Default")
      (node (ref "C.BC1") (pin "1") (pinfunction "1_1") (pintype "passive"))
      (node (ref "U.BC1") (pin "BST") (pinfunction "BST_BST") (pintype "bidirectional"))
    )
    (net (code "24") (name "Net-(C.BC2-Pad2)") (class "Default")
      (node (ref "C.BC2") (pin "2") (pinfunction "2_2") (pintype "passive"))
      (node (ref "R.BC1") (pin "2") (pinfunction "2_2") (pintype "passive"))
      (node (ref "SJ.BC1") (pin "2") (pinfunction "2_2") (pintype "passive"))
      (node (ref "U.BC1") (pin "VCC") (pinfunction "VCC_VCC") (pintype "bidirectional"))
    )
    (net (code "25") (name "Net-(C.BC5-Pad2)") (class "Default")
      (node (ref "C.BC5") (pin "2") (pinfunction "2_2") (pintype "passive"))
      (node (ref "U.BC1") (pin "TMR") (pinfunction "TMR_TMR") (pintype "bidirectional"))
    )
    (net (code "26") (name "Net-(C.DS1-+)") (class "Default")
      (node (ref "C.DS1") (pin "A$1") (pinfunction "+_A$1") (pintype "passive"))
      (node (ref "F.DS1") (pin "2") (pinfunction "2_2") (pintype "passive"))
      (node (ref "X.DS1") (pin "P$1") (pinfunction "1_P$1") (pintype "passive"))
    )
    (net (code "27") (name "Net-(C.SI2*-Pad1)") (class "Default")
      (node (ref "C.SI2*") (pin "1") (pinfunction "1_1") (pintype "passive"))
      (node (ref "R.SI1*") (pin "1") (pinfunction "1_1") (pintype "passive"))
      (node (ref "SV2") (pin "1") (pinfunction "1_1") (pintype "passive"))
    )
    (net (code "28") (name "Net-(C.SI3*-Pad1)") (class "Default")
      (node (ref "C.SI3*") (pin "1") (pinfunction "1_1") (pintype "passive"))
      (node (ref "R.SI2*") (pin "1") (pinfunction "1_1") (pintype "passive"))
      (node (ref "SV1") (pin "1") (pinfunction "1_1") (pintype "passive"))
    )
    (net (code "29") (name "Net-(D.USB1-PadA)") (class "Default")
      (node (ref "D.USB1") (pin "A") (pinfunction "A_A") (pintype "passive"))
      (node (ref "R.ESP1") (pin "1") (pinfunction "1_1") (pintype "passive"))
    )
    (net (code "30") (name "Net-(D.VI1-PadA)") (class "Default")
      (node (ref "D.VI1") (pin "A") (pinfunction "A_A") (pintype "passive"))
      (node (ref "R.VI1") (pin "1") (pinfunction "1_1") (pintype "passive"))
    )
    (net (code "31") (name "Net-(D.ZZ1-PadA)") (class "Default")
      (node (ref "D.ZZ1") (pin "A") (pinfunction "A_A") (pintype "passive"))
      (node (ref "R.ZZ1") (pin "1") (pinfunction "1_1") (pintype "passive"))
    )
    (net (code "32") (name "Net-(L.BC1-1)") (class "Default")
      (node (ref "C.BC1") (pin "2") (pinfunction "2_2") (pintype "passive"))
      (node (ref "L.BC1") (pin "P$1") (pinfunction "1_P$1") (pintype "passive"))
      (node (ref "U.BC1") (pin "SW") (pinfunction "SW_SW") (pintype "bidirectional"))
    )
    (net (code "33") (name "Net-(L.BC1-2)") (class "Default")
      (node (ref "L.BC1") (pin "P$2") (pinfunction "2_P$2") (pintype "passive"))
      (node (ref "R.BC3") (pin "1") (pinfunction "1_1") (pintype "passive"))
      (node (ref "U.BC1") (pin "CSP") (pinfunction "CSP_CSP") (pintype "bidirectional"))
    )
    (net (code "34") (name "Net-(L.DS1-1)") (class "Default")
      (node (ref "C.DS5") (pin "2") (pinfunction "2_2") (pintype "passive"))
      (node (ref "L.DS1") (pin "P$1") (pinfunction "1_P$1") (pintype "passive"))
      (node (ref "U.DS2") (pin "5") (pinfunction "SW_5") (pintype "bidirectional"))
    )
    (net (code "35") (name "Net-(L.DS1-2)") (class "Default")
      (node (ref "C.DS10") (pin "2") (pinfunction "2_2") (pintype "passive"))
      (node (ref "C.DS6") (pin "1") (pinfunction "1_1") (pintype "passive"))
      (node (ref "C.DS8") (pin "1") (pinfunction "1_1") (pintype "passive"))
      (node (ref "L.DS1") (pin "P$2") (pinfunction "2_P$2") (pintype "passive"))
      (node (ref "Q.DS2") (pin "A") (pinfunction "A_A") (pintype "passive"))
      (node (ref "TP2") (pin "TP") (pinfunction "TP_TP") (pintype "input"))
      (node (ref "U.DS2") (pin "1") (pinfunction "FB_1") (pintype "bidirectional"))
    )
    (net (code "36") (name "Net-(L.ZZ1-1)") (class "Default")
      (node (ref "C.ZZ3") (pin "2") (pinfunction "2_2") (pintype "passive"))
      (node (ref "L.ZZ1") (pin "P$1") (pinfunction "1_P$1") (pintype "passive"))
      (node (ref "U.ZZ1") (pin "5") (pinfunction "SW_5") (pintype "bidirectional"))
    )
    (net (code "37") (name "Net-(Q.BI1-D)") (class "Default")
      (node (ref "Q.BI1") (pin "3") (pinfunction "D_3") (pintype "passive"))
      (node (ref "R.BI3") (pin "2") (pinfunction "2_2") (pintype "passive"))
    )
    (net (code "38") (name "Net-(Q.BI1-S)") (class "Default")
      (node (ref "C.BI2") (pin "1") (pinfunction "1_1") (pintype "passive"))
      (node (ref "Q.BI1") (pin "2") (pinfunction "S_2") (pintype "passive"))
      (node (ref "X.BI1") (pin "2") (pinfunction "2_2") (pintype "passive"))
      (node (ref "X.BI2") (pin "1") (pinfunction "1_1") (pintype "passive"))
    )
    (net (code "39") (name "Net-(Q.BI2-D)") (class "Default")
      (node (ref "Q.BI2") (pin "3") (pinfunction "D_3") (pintype "passive"))
      (node (ref "R.BI1") (pin "2") (pinfunction "2_2") (pintype "passive"))
    )
    (net (code "40") (name "Net-(Q.YY1A-D)") (class "Default")
      (node (ref "C.YY2") (pin "2") (pinfunction "2_2") (pintype "passive"))
      (node (ref "Q.YY1") (pin "D$1B") (pinfunction "D_D$1B") (pintype "passive"))
      (node (ref "Q.YY2") (pin "3") (pinfunction "S_3") (pintype "passive"))
      (node (ref "U.YY1") (pin "13") (pinfunction "VIN1_13") (pintype "input"))
    )
    (net (code "41") (name "Net-(Q.YY1B-D)") (class "Default")
      (node (ref "C.YY3") (pin "1") (pinfunction "1_1") (pintype "passive"))
      (node (ref "Q.YY1") (pin "D$2A") (pinfunction "D_D$2A") (pintype "passive"))
      (node (ref "Q.YY2") (pin "1") (pinfunction "S_1") (pintype "passive"))
      (node (ref "U.YY1") (pin "4") (pinfunction "VIN2_4") (pintype "input"))
    )
    (net (code "42") (name "Net-(Q.YY2A-G)") (class "Default")
      (node (ref "Q.YY2") (pin "2") (pinfunction "G_2") (pintype "passive"))
      (node (ref "U.YY1") (pin "5") (pinfunction "GATE2_5") (pintype "output"))
    )
    (net (code "43") (name "Net-(Q.YY2B-G)") (class "Default")
      (node (ref "Q.YY2") (pin "4") (pinfunction "G_4") (pintype "passive"))
      (node (ref "U.YY1") (pin "12") (pinfunction "GATE1_12") (pintype "output"))
    )
    (net (code "44") (name "Net-(R.BC1-Pad1)") (class "Default")
      (node (ref "R.BC1") (pin "1") (pinfunction "1_1") (pintype "passive"))
      (node (ref "R.BC2") (pin "2") (pinfunction "2_2") (pintype "passive"))
      (node (ref "U.BC1") (pin "NTC") (pinfunction "NTC_NTC") (pintype "bidirectional"))
    )
    (net (code "45") (name "Net-(SJ.BC1-Pad1)") (class "Default")
      (node (ref "SJ.BC1") (pin "1") (pinfunction "1_1") (pintype "passive"))
      (node (ref "U.BC1") (pin "SEL") (pinfunction "SEL_SEL") (pintype "bidirectional"))
    )
    (net (code "46") (name "Net-(U.DS1-3Y)") (class "Default")
      (node (ref "C.DS4*") (pin "1") (pinfunction "1_1") (pintype "passive"))
      (node (ref "R.DS1*") (pin "2") (pinfunction "2_2") (pintype "passive"))
      (node (ref "U.DS1") (pin "8") (pinfunction "3Y_8") (pintype "passive"))
    )
    (net (code "47") (name "Net-(U.DS1-4Y)") (class "Default")
      (node (ref "C.DS2*") (pin "1") (pinfunction "1_1") (pintype "passive"))
      (node (ref "R.DS2*") (pin "2") (pinfunction "2_2") (pintype "passive"))
      (node (ref "U.DS1") (pin "11") (pinfunction "4Y_11") (pintype "passive"))
    )
    (net (code "48") (name "Net-(U.DS2-BST)") (class "Default")
      (node (ref "C.DS5") (pin "1") (pinfunction "1_1") (pintype "passive"))
      (node (ref "U.DS2") (pin "6") (pinfunction "BST_6") (pintype "bidirectional"))
    )
    (net (code "49") (name "Net-(U.EC1-FB)") (class "Default")
      (node (ref "R.EC1") (pin "2") (pinfunction "2_2") (pintype "passive"))
      (node (ref "R.EC3") (pin "2") (pinfunction "2_2") (pintype "passive"))
      (node (ref "U.EC1") (pin "2") (pinfunction "FB_2") (pintype "input"))
    )
    (net (code "50") (name "Net-(U.EC1-RT_CLK)") (class "Default")
      (node (ref "R.EC2") (pin "2") (pinfunction "2_2") (pintype "passive"))
      (node (ref "U.EC1") (pin "24") (pinfunction "RT_CLK_24") (pintype "input"))
    )
    (net (code "51") (name "Net-(U.EC1-SW)") (class "Default")
      (node (ref "U.EC1") (pin "16") (pinfunction "SW_2_16") (pintype "output"))
      (node (ref "U.EC1") (pin "17") (pinfunction "SW_17") (pintype "output"))
    )
    (net (code "52") (name "Net-(U.EC1-TT)") (class "Default")
      (node (ref "R.EC4") (pin "1") (pinfunction "1_1") (pintype "passive"))
      (node (ref "U.EC1") (pin "5") (pinfunction "TT_5") (pintype "passive"))
    )
    (net (code "53") (name "Net-(U.TK1-VCC)") (class "Default")
      (node (ref "C.TK1") (pin "2") (pinfunction "2_2") (pintype "passive"))
      (node (ref "R.TK1*") (pin "1") (pinfunction "1_1") (pintype "passive"))
      (node (ref "R.TK2") (pin "1") (pinfunction "1_1") (pintype "passive"))
      (node (ref "R.TK3") (pin "1") (pinfunction "1_1") (pintype "passive"))
      (node (ref "U.TK1") (pin "P$1") (pinfunction "VCC_P$1") (pintype "bidirectional"))
    )
    (net (code "54") (name "Net-(U.YY1-CPO1)") (class "Default")
      (node (ref "C.YY2") (pin "1") (pinfunction "1_1") (pintype "passive"))
      (node (ref "U.YY1") (pin "11") (pinfunction "CPO1_11") (pintype "output"))
    )
    (net (code "55") (name "Net-(U.YY1-CPO2)") (class "Default")
      (node (ref "C.YY3") (pin "2") (pinfunction "2_2") (pintype "passive"))
      (node (ref "U.YY1") (pin "6") (pinfunction "CPO2_6") (pintype "output"))
    )
    (net (code "56") (name "Net-(U.YY1-VCC)") (class "Default")
      (node (ref "C.YY1") (pin "1") (pinfunction "1_1") (pintype "passive"))
      (node (ref "U.YY1") (pin "14") (pinfunction "VCC_14") (pintype "power_in"))
    )
    (net (code "57") (name "Net-(U.ZZ1-BST)") (class "Default")
      (node (ref "C.ZZ3") (pin "1") (pinfunction "1_1") (pintype "passive"))
      (node (ref "U.ZZ1") (pin "6") (pinfunction "BST_6") (pintype "bidirectional"))
    )
    (net (code "58") (name "Net-(U.ZZ1-EN)") (class "Default")
      (node (ref "C.ZZ2") (pin "1") (pinfunction "1_1") (pintype "passive"))
      (node (ref "C.ZZ5") (pin "2") (pinfunction "2_2") (pintype "passive"))
      (node (ref "Q.ZZ1") (pin "C") (pinfunction "C_C") (pintype "passive"))
      (node (ref "Q.ZZ2") (pin "C") (pinfunction "C_C") (pintype "passive"))
      (node (ref "Q.ZZ3") (pin "C") (pinfunction "C_C") (pintype "passive"))
      (node (ref "R.ZZ2") (pin "1") (pinfunction "1_1") (pintype "passive"))
      (node (ref "R.ZZ3") (pin "1") (pinfunction "1_1") (pintype "passive"))
      (node (ref "TP12") (pin "TP") (pinfunction "TP_TP") (pintype "input"))
      (node (ref "U.ZZ1") (pin "2") (pinfunction "EN_2") (pintype "bidirectional"))
      (node (ref "U.ZZ1") (pin "3") (pinfunction "VIN_3") (pintype "bidirectional"))
    )
    (net (code "59") (name "Net-(X.DS1-2)") (class "Default")
      (node (ref "R.DS1*") (pin "1") (pinfunction "1_1") (pintype "passive"))
      (node (ref "X.DS1") (pin "P$2") (pinfunction "2_P$2") (pintype "passive"))
    )
    (net (code "60") (name "Net-(X.DS1-3)") (class "Default")
      (node (ref "R.DS2*") (pin "1") (pinfunction "1_1") (pintype "passive"))
      (node (ref "X.DS1") (pin "P$3") (pinfunction "3_P$3") (pintype "passive"))
    )
    (net (code "61") (name "RAWSENSE") (class "Default")
      (node (ref "R.VI2") (pin "1") (pinfunction "1_1") (pintype "passive"))
      (node (ref "R.VI3") (pin "2") (pinfunction "2_2") (pintype "passive"))
      (node (ref "U.ESP1") (pin "6") (pinfunction "IO34_6") (pintype "bidirectional"))
    )
    (net (code "62") (name "RESET") (class "Default")
      (node (ref "R.ESP2") (pin "2") (pinfunction "2_2") (pintype "passive"))
      (node (ref "U.ESP1") (pin "3") (pinfunction "EN_3") (pintype "input"))
      (node (ref "X.ESP6") (pin "P$1") (pinfunction "1_P$1") (pintype "passive"))
    )
    (net (code "63") (name "SERVO1") (class "Default")
      (node (ref "R.SI1*") (pin "2") (pinfunction "2_2") (pintype "passive"))
      (node (ref "U.ESP1") (pin "37") (pinfunction "IO23_37") (pintype "bidirectional"))
    )
    (net (code "64") (name "SERVO2") (class "Default")
      (node (ref "R.SI2*") (pin "2") (pinfunction "2_2") (pintype "passive"))
      (node (ref "U.ESP1") (pin "10") (pinfunction "IO25_10") (pintype "bidirectional"))
    )
    (net (code "65") (name "SYS_POWER") (class "Default")
      (node (ref "C.DS7") (pin "1") (pinfunction "1_1") (pintype "passive"))
      (node (ref "C.DS9") (pin "2") (pinfunction "2_2") (pintype "passive"))
      (node (ref "C.SI1") (pin "2") (pinfunction "2_2") (pintype "passive"))
      (node (ref "C.YY4") (pin "1") (pinfunction "1_1") (pintype "passive"))
      (node (ref "Q.YY2") (pin "5") (pinfunction "D_5") (pintype "passive"))
      (node (ref "Q.YY2") (pin "6") (pinfunction "D_6") (pintype "passive"))
      (node (ref "Q.YY2") (pin "7") (pinfunction "D_7") (pintype "passive"))
      (node (ref "Q.YY2") (pin "8") (pinfunction "D_8") (pintype "passive"))
      (node (ref "R.YY2") (pin "2") (pinfunction "2_2") (pintype "passive"))
      (node (ref "SV1") (pin "2") (pinfunction "2_2") (pintype "passive"))
      (node (ref "SV2") (pin "2") (pinfunction "2_2") (pintype "passive"))
      (node (ref "SV3") (pin "2") (pinfunction "2_2") (pintype "passive"))
      (node (ref "U.DS2") (pin "2") (pinfunction "EN_2") (pintype "bidirectional"))
      (node (ref "U.DS2") (pin "3") (pinfunction "VIN_3") (pintype "bidirectional"))
      (node (ref "U.YY1") (pin "10") (pinfunction "OUT1_10") (pintype "output"))
      (node (ref "U.YY1") (pin "7") (pinfunction "OUT2_7") (pintype "output"))
    )
    (net (code "66") (name "SYS_SENSE") (class "Default")
      (node (ref "R.YY1") (pin "2") (pinfunction "2_2") (pintype "passive"))
      (node (ref "R.YY2") (pin "1") (pinfunction "1_1") (pintype "passive"))
      (node (ref "U.ESP1") (pin "7") (pinfunction "IO35_7") (pintype "bidirectional"))
    )
    (net (code "67") (name "VBAT") (class "Default")
      (node (ref "C.BC4") (pin "1") (pinfunction "1_1") (pintype "passive"))
      (node (ref "C.BI1") (pin "1") (pinfunction "1_1") (pintype "passive"))
      (node (ref "Q.BI2") (pin "2") (pinfunction "S_2") (pintype "passive"))
      (node (ref "Q.YY1") (pin "P$1") (pinfunction "S_P$1") (pintype "passive"))
      (node (ref "Q.ZZ3") (pin "A") (pinfunction "A_A") (pintype "passive"))
      (node (ref "R.BC3") (pin "2") (pinfunction "2_2") (pintype "passive"))
      (node (ref "TP1") (pin "TP") (pinfunction "TP_TP") (pintype "input"))
      (node (ref "U.BC1") (pin "BAT") (pinfunction "BAT_BAT") (pintype "bidirectional"))
      (node (ref "X.BI1") (pin "1") (pinfunction "1_1") (pintype "passive"))
    )
    (net (code "68") (name "VCONV") (class "Default")
      (node (ref "C.EC5") (pin "1") (pinfunction "1_1") (pintype "passive"))
      (node (ref "C.EC6") (pin "P$2") (pinfunction "+_P$2") (pintype "passive"))
      (node (ref "C.EC7") (pin "2") (pinfunction "2_2") (pintype "passive"))
      (node (ref "Q.YY1") (pin "P$3") (pinfunction "S_P$3") (pintype "passive"))
      (node (ref "Q.ZZ1") (pin "A") (pinfunction "A_A") (pintype "passive"))
      (node (ref "R.EC1") (pin "1") (pinfunction "1_1") (pintype "passive"))
      (node (ref "TP4") (pin "TP") (pinfunction "TP_TP") (pintype "input"))
      (node (ref "U.EC1") (pin "1") (pinfunction "VOUT_2_1") (pintype "power_in"))
      (node (ref "U.EC1") (pin "8") (pinfunction "VOUT_8") (pintype "power_in"))
    )
    (net (code "69") (name "VPROG") (class "Default")
      (node (ref "Q.DS1") (pin "A") (pinfunction "A_A") (pintype "passive"))
      (node (ref "Q.ZZ2") (pin "A") (pinfunction "A_A") (pintype "passive"))
      (node (ref "X.ESP6") (pin "P$6") (pinfunction "6_P$6") (pintype "passive"))
    )
    (net (code "70") (name "VRAW") (class "Default")
      (node (ref "C.BC3") (pin "1") (pinfunction "1_1") (pintype "passive"))
      (node (ref "C.EC1") (pin "2") (pinfunction "2_2") (pintype "passive"))
      (node (ref "C.EC2") (pin "2") (pinfunction "2_2") (pintype "passive"))
      (node (ref "C.EC3") (pin "+") (pinfunction "+_+") (pintype "passive"))
      (node (ref "C.EC4") (pin "+") (pinfunction "+_+") (pintype "passive"))
      (node (ref "C.VI3") (pin "1") (pinfunction "1_1") (pintype "passive"))
      (node (ref "Q.VI1") (pin "1") (pinfunction "K2_1") (pintype "passive"))
      (node (ref "R.VI1") (pin "2") (pinfunction "2_2") (pintype "passive"))
      (node (ref "R.VI2") (pin "2") (pinfunction "2_2") (pintype "passive"))
      (node (ref "U.BC1") (pin "VIN") (pinfunction "VIN_VIN") (pintype "bidirectional"))
      (node (ref "U.EC1") (pin "11") (pinfunction "VIN_2_11") (pintype "power_in"))
      (node (ref "U.EC1") (pin "22") (pinfunction "VIN_22") (pintype "power_in"))
      (node (ref "X.VI1") (pin "2") (pinfunction "2_2") (pintype "passive"))
    )
    (net (code "71") (name "unconnected-(Q.VI1-K1-Pad2)") (class "Default")
      (node (ref "Q.VI1") (pin "2") (pinfunction "K1_2") (pintype "passive"))
    )
    (net (code "72") (name "unconnected-(U.BC1-PadCELL)") (class "Default")
      (node (ref "U.BC1") (pin "CELL") (pinfunction "CELL_CELL") (pintype "bidirectional"))
    )
    (net (code "73") (name "unconnected-(U.BC1-~{EN}-Pad!EN)") (class "Default")
      (node (ref "U.BC1") (pin "!EN") (pinfunction "~{EN}_!EN") (pintype "bidirectional"))
    )
    (net (code "74") (name "unconnected-(U.DS1-1Y-Pad3)") (class "Default")
      (node (ref "U.DS1") (pin "3") (pinfunction "1Y_3") (pintype "passive"))
    )
    (net (code "75") (name "unconnected-(U.DS1-2Y-Pad6)") (class "Default")
      (node (ref "U.DS1") (pin "6") (pinfunction "2Y_6") (pintype "passive"))
    )
    (net (code "76") (name "unconnected-(U.EC1-DNC-Pad4)") (class "Default")
      (node (ref "U.EC1") (pin "4") (pinfunction "DNC_4") (pintype "passive"))
    )
    (net (code "77") (name "unconnected-(U.EC1-EN-Pad10)") (class "Default")
      (node (ref "U.EC1") (pin "10") (pinfunction "EN_10") (pintype "input"))
    )
    (net (code "78") (name "unconnected-(U.EC1-PGOOD-Pad7)") (class "Default")
      (node (ref "U.EC1") (pin "7") (pinfunction "PGOOD_7") (pintype "passive"))
    )
    (net (code "79") (name "unconnected-(U.EC1-SS_TRK-Pad6)") (class "Default")
      (node (ref "U.EC1") (pin "6") (pinfunction "SS_TRK_6") (pintype "passive"))
    )
    (net (code "80") (name "unconnected-(U.ESP1-IO2-Pad24)") (class "Default")
      (node (ref "U.ESP1") (pin "24") (pinfunction "IO2_24") (pintype "bidirectional"))
    )
    (net (code "81") (name "unconnected-(U.ESP1-IO5-Pad29)") (class "Default")
      (node (ref "U.ESP1") (pin "29") (pinfunction "IO5_29") (pintype "bidirectional"))
    )
    (net (code "82") (name "unconnected-(U.ESP1-IO15-Pad23)") (class "Default")
      (node (ref "U.ESP1") (pin "23") (pinfunction "IO15_23") (pintype "bidirectional"))
    )
    (net (code "83") (name "unconnected-(U.ESP1-IO18-Pad30)") (class "Default")
      (node (ref "U.ESP1") (pin "30") (pinfunction "IO18_30") (pintype "bidirectional"))
    )
    (net (code "84") (name "unconnected-(U.ESP1-IO20-Pad32)") (class "Default")
      (node (ref "U.ESP1") (pin "32") (pinfunction "IO20_32") (pintype "bidirectional"))
    )
    (net (code "85") (name "unconnected-(U.ESP1-IO32-Pad8)") (class "Default")
      (node (ref "U.ESP1") (pin "8") (pinfunction "IO32_8") (pintype "bidirectional"))
    )
    (net (code "86") (name "unconnected-(U.ESP1-IO33-Pad9)") (class "Default")
      (node (ref "U.ESP1") (pin "9") (pinfunction "IO33_9") (pintype "bidirectional"))
    )
    (net (code "87") (name "unconnected-(U.ESP1-SCL{slash}CLK-Pad20)") (class "Default")
      (node (ref "U.ESP1") (pin "20") (pinfunction "SCL/CLK_20") (pintype "bidirectional"))
    )
    (net (code "88") (name "unconnected-(U.ESP1-SCS{slash}CMD-Pad19)") (class "Default")
      (node (ref "U.ESP1") (pin "19") (pinfunction "SCS/CMD_19") (pintype "bidirectional"))
    )
    (net (code "89") (name "unconnected-(U.ESP1-SDI{slash}SD1-Pad22)") (class "Default")
      (node (ref "U.ESP1") (pin "22") (pinfunction "SDI/SD1_22") (pintype "bidirectional"))
    )
    (net (code "90") (name "unconnected-(U.ESP1-SDO{slash}SD0-Pad21)") (class "Default")
      (node (ref "U.ESP1") (pin "21") (pinfunction "SDO/SD0_21") (pintype "bidirectional"))
    )
    (net (code "91") (name "unconnected-(U.ESP1-SHD{slash}SD2-Pad17)") (class "Default")
      (node (ref "U.ESP1") (pin "17") (pinfunction "SHD/SD2_17") (pintype "bidirectional"))
    )
    (net (code "92") (name "unconnected-(U.ESP1-SWP{slash}SD3-Pad18)") (class "Default")
      (node (ref "U.ESP1") (pin "18") (pinfunction "SWP/SD3_18") (pintype "bidirectional"))
    )
    (net (code "93") (name "unconnected-(U.YY1-NC-Pad3)") (class "Default")
      (node (ref "U.YY1") (pin "3") (pinfunction "NC_3") (pintype "no_connect"))
    )
    (net (code "94") (name "unconnected-(U.YY1-NC_2-Pad2)") (class "Default")
      (node (ref "U.YY1") (pin "2") (pinfunction "NC_2_2") (pintype "no_connect"))
    )
    (net (code "95") (name "unconnected-(X.ESP6-4-PadP$4)") (class "Default")
      (node (ref "X.ESP6") (pin "P$4") (pinfunction "4_P$4") (pintype "passive"))
    )
  )
)
